# Arduino_Shield.net
KiCad netlist of a schematic drawn in Altium Designer
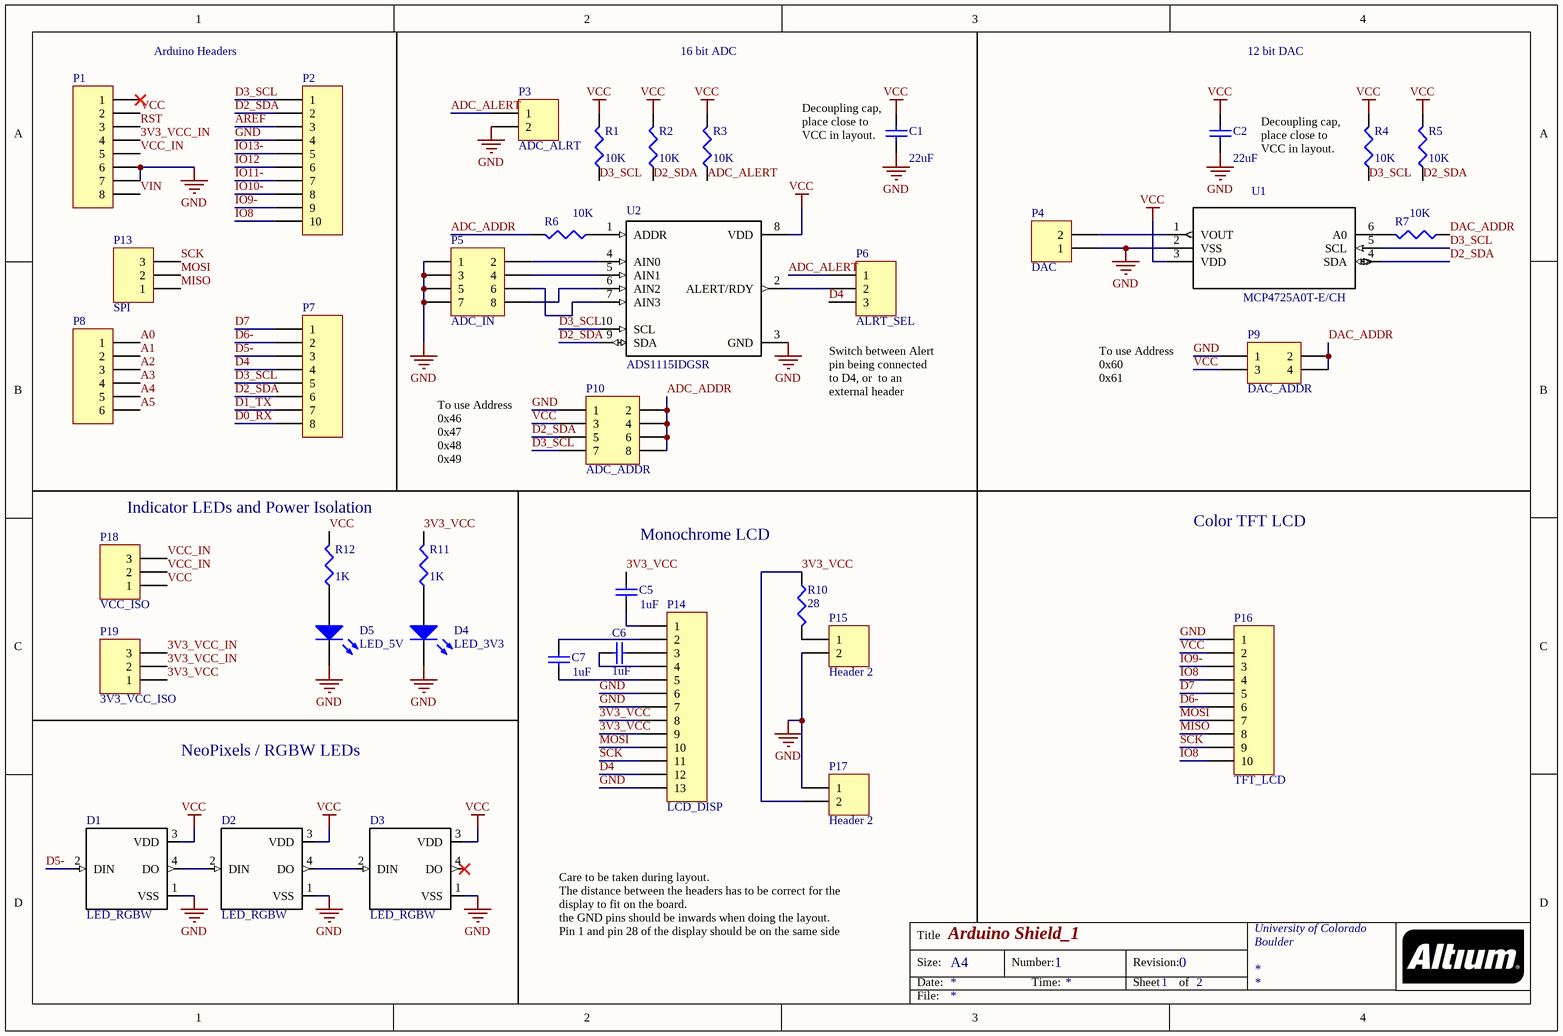
[diagram p0: Arduino_Shield.SchDoc]

(export (version "E")
  (design (tool "Eeschema 10.0.6"))
  (components
    (comp (ref "C1")
      (value "22uF")
      (footprint "C1206")
      (description "Capacitor (Semiconductor SIM Model)")
      (fields
        (field (name "DIGIKEYPARTNO") "1276-1079-1-ND")
        (field (name "Comment") "Cap Semi")
        (field (name "PUBLISHER") "Altium Limited")
      )
      (libsource (lib "Miscellaneous Devices") (part "Cap Semi"))
    )
    (comp (ref "C2")
      (value "22uF")
      (footprint "C1206")
      (description "Capacitor (Semiconductor SIM Model)")
      (fields
        (field (name "DIGIKEYPARTNO") "1276-1079-1-ND")
        (field (name "Comment") "Cap Semi")
        (field (name "PUBLISHER") "Altium Limited")
      )
      (libsource (lib "Miscellaneous Devices") (part "Cap Semi"))
    )
    (comp (ref "C5")
      (value "1uF")
      (footprint "C1206")
      (description "Capacitor (Semiconductor SIM Model)")
      (fields
        (field (name "DIGIKEYPARTNO") "732-7692-1-ND")
        (field (name "Comment") "Cap Semi")
        (field (name "PUBLISHER") "Altium Limited")
      )
      (libsource (lib "Miscellaneous Devices") (part "Cap Semi"))
    )
    (comp (ref "C6")
      (value "1uF")
      (footprint "C1206")
      (description "Capacitor (Semiconductor SIM Model)")
      (fields
        (field (name "DIGIKEYPARTNO") "732-7692-1-ND")
        (field (name "Comment") "Cap Semi")
        (field (name "PUBLISHER") "Altium Limited")
      )
      (libsource (lib "Miscellaneous Devices") (part "Cap Semi"))
    )
    (comp (ref "C7")
      (value "1uF")
      (footprint "C1206")
      (description "Capacitor (Semiconductor SIM Model)")
      (fields
        (field (name "DIGIKEYPARTNO") "732-7692-1-ND")
        (field (name "Comment") "Cap Semi")
        (field (name "PUBLISHER") "Altium Limited")
      )
      (libsource (lib "Miscellaneous Devices") (part "Cap Semi"))
    )
    (comp (ref "D1")
      (value "LED_RGBW")
      (footprint "*LED_IN-PI554FCH")
      (description "5050RGB with integrated IC built in 4 PIN Â•Viewing angle: 120 degrees")
      (fields (field (name "MP") "IN-PI554FCH") (field (name "MF") "Inolux"))
      (libsource (lib "IN-PI554FCH") (part "IN-PI554FCH"))
    )
    (comp (ref "D2")
      (value "LED_RGBW")
      (footprint "*LED_IN-PI554FCH")
      (description "5050RGB with integrated IC built in 4 PIN Â•Viewing angle: 120 degrees")
      (fields (field (name "MP") "IN-PI554FCH") (field (name "MF") "Inolux"))
      (libsource (lib "IN-PI554FCH") (part "IN-PI554FCH"))
    )
    (comp (ref "D3")
      (value "LED_RGBW")
      (footprint "*LED_IN-PI554FCH")
      (description "5050RGB with integrated IC built in 4 PIN Â•Viewing angle: 120 degrees")
      (fields (field (name "MP") "IN-PI554FCH") (field (name "MF") "Inolux"))
      (libsource (lib "IN-PI554FCH") (part "IN-PI554FCH"))
    )
    (comp (ref "D4")
      (value "LED_3V3")
      (footprint "3.2X1.6X1.1")
      (description "Typical RED, GREEN, YELLOW, AMBER GaAs LED")
      (fields (field (name "PUBLISHER") "Altium Limited"))
      (libsource (lib "Miscellaneous Devices") (part "LED2"))
    )
    (comp (ref "D5")
      (value "LED_5V")
      (footprint "3.2X1.6X1.1")
      (description "Typical RED, GREEN, YELLOW, AMBER GaAs LED")
      (fields (field (name "PUBLISHER") "Altium Limited"))
      (libsource (lib "Miscellaneous Devices") (part "LED2"))
    )
    (comp (ref "P1")
      (value "P4")
      (footprint "HDR1X8")
      (description "Header, 8-Pin")
      (fields (field (name "DIGIKEYPARTNO") "1568-1413-ND") (field (name "PUBLISHER") "Altium Limited"))
      (libsource (lib "Miscellaneous Connectors") (part "Header 8"))
    )
    (comp (ref "P2")
      (value "P1")
      (footprint "HDR1X10")
      (description "Header, 10-Pin")
      (fields (field (name "DIGIKEYPARTNO") "1568-1413-ND") (field (name "PUBLISHER") "Altium Limited"))
      (libsource (lib "Miscellaneous Connectors") (part "Header 10"))
    )
    (comp (ref "P3")
      (value "ADC_ALRT")
      (footprint "HDR1X2")
      (description "Header, 2-Pin")
      (fields (field (name "DIGIKEYPARTNO") "732-5315-ND") (field (name "PUBLISHER") "Altium Limited"))
      (libsource (lib "") (part "Header 2_1"))
    )
    (comp (ref "P4")
      (value "DAC")
      (footprint "HDR1X2")
      (description "Header, 2-Pin")
      (fields (field (name "DIGIKEYPARTNO") "732-5315-ND") (field (name "PUBLISHER") "Altium Limited"))
      (libsource (lib "Miscellaneous Connectors") (part "Header 2"))
    )
    (comp (ref "P5")
      (value "ADC_IN")
      (footprint "HDR2X4")
      (description "Header, 4-Pin, Dual row")
      (fields (field (name "DIGIKEYPARTNO") "952-2121-ND") (field (name "PUBLISHER") "Altium Limited"))
      (libsource (lib "Miscellaneous Connectors") (part "Header 4X2"))
    )
    (comp (ref "P6")
      (value "ALRT_SEL")
      (footprint "HDR1X3")
      (description "Header, 3-Pin")
      (fields (field (name "DIGIKEYPARTNO") "732-5315-ND") (field (name "PUBLISHER") "Altium Limited"))
      (libsource (lib "Miscellaneous Connectors") (part "Header 3"))
    )
    (comp (ref "P7")
      (value "P2")
      (footprint "HDR1X8")
      (description "Header, 8-Pin")
      (fields (field (name "DIGIKEYPARTNO") "1568-1413-ND") (field (name "PUBLISHER") "Altium Limited"))
      (libsource (lib "") (part "Header 8_1"))
    )
    (comp (ref "P8")
      (value "P3")
      (footprint "HDR1X6")
      (description "Header, 6-Pin")
      (fields (field (name "DIGIKEYPARTNO") "1568-1413-ND") (field (name "PUBLISHER") "Altium Limited"))
      (libsource (lib "Miscellaneous Connectors") (part "Header 6"))
    )
    (comp (ref "P9")
      (value "DAC_ADDR")
      (footprint "HDR2X2")
      (description "Header, 2-Pin, Dual row")
      (fields (field (name "DIGIKEYPARTNO") "952-2121-ND") (field (name "PUBLISHER") "Altium Limited"))
      (libsource (lib "Miscellaneous Connectors") (part "Header 2X2"))
    )
    (comp (ref "P10")
      (value "ADC_ADDR")
      (footprint "HDR2X4")
      (description "Header, 4-Pin, Dual row")
      (fields (field (name "DIGIKEYPARTNO") "952-2121-ND") (field (name "PUBLISHER") "Altium Limited"))
      (libsource (lib "Miscellaneous Connectors") (part "Header 4X2"))
    )
    (comp (ref "P13")
      (value "SPI")
      (footprint "HDR1X3")
      (description "Header, 3-Pin")
      (fields (field (name "DIGIKEYPARTNO") "1568-1413-ND") (field (name "PUBLISHER") "Altium Limited"))
      (libsource (lib "") (part "Header 3_1"))
    )
    (comp (ref "P14")
      (value "LCD_DISP")
      (footprint "HDR1X13")
      (description "Header, 13-Pin")
      (fields (field (name "DIGIKEYPARTNO") "1212-1179-ND") (field (name "PUBLISHER") "Altium Limited"))
      (libsource (lib "Miscellaneous Connectors") (part "Header 13"))
    )
    (comp (ref "P15")
      (value "Header 2")
      (footprint "HDR1X2")
      (description "Header, 2-Pin")
      (fields (field (name "DIGIKEYPARTNO") "1212-1179-ND") (field (name "PUBLISHER") "Altium Limited"))
      (libsource (lib "") (part "Header 2_1"))
    )
    (comp (ref "P16")
      (value "TFT_LCD")
      (footprint "HDR1X10")
      (description "Header, 10-Pin")
      (fields (field (name "DIGIKEYPARTNO") "1212-1179-ND") (field (name "PUBLISHER") "Altium Limited"))
      (libsource (lib "Miscellaneous Connectors") (part "Header 10"))
    )
    (comp (ref "P17")
      (value "Header 2")
      (footprint "HDR1X2")
      (description "Header, 2-Pin")
      (fields (field (name "DIGIKEYPARTNO") "1212-1179-ND") (field (name "PUBLISHER") "Altium Limited"))
      (libsource (lib "") (part "Header 2_1"))
    )
    (comp (ref "P18")
      (value "VCC_ISO")
      (footprint "HDR1X3")
      (description "Header, 3-Pin")
      (fields (field (name "DIGIKEYPARTNO") "1568-1413-ND") (field (name "PUBLISHER") "Altium Limited"))
      (libsource (lib "") (part "Header 3_1"))
    )
    (comp (ref "P19")
      (value "3V3_VCC_ISO")
      (footprint "HDR1X3")
      (description "Header, 3-Pin")
      (fields (field (name "DIGIKEYPARTNO") "1568-1413-ND") (field (name "PUBLISHER") "Altium Limited"))
      (libsource (lib "") (part "Header 3_1"))
    )
    (comp (ref "R1")
      (value "10K")
      (footprint "C1206")
      (description "Resistor")
      (fields
        (field (name "DIGIKEYPARTNO") "RMCF1206JT10K0CT-ND")
        (field (name "Comment") "Res3")
        (field (name "PUBLISHER") "Altium Limited")
      )
      (libsource (lib "Miscellaneous Devices") (part "Res3"))
    )
    (comp (ref "R2")
      (value "10K")
      (footprint "C1206")
      (description "Resistor")
      (fields
        (field (name "DIGIKEYPARTNO") "RMCF1206JT10K0CT-ND")
        (field (name "Comment") "Res3")
        (field (name "PUBLISHER") "Altium Limited")
      )
      (libsource (lib "Miscellaneous Devices") (part "Res3"))
    )
    (comp (ref "R3")
      (value "10K")
      (footprint "C1206")
      (description "Resistor")
      (fields
        (field (name "DIGIKEYPARTNO") "RMCF1206JT10K0CT-ND")
        (field (name "Comment") "Res3")
        (field (name "PUBLISHER") "Altium Limited")
      )
      (libsource (lib "Miscellaneous Devices") (part "Res3"))
    )
    (comp (ref "R4")
      (value "10K")
      (footprint "C1206")
      (description "Resistor")
      (fields
        (field (name "DIGIKEYPARTNO") "RMCF1206JT10K0CT-ND")
        (field (name "Comment") "Res3")
        (field (name "PUBLISHER") "Altium Limited")
      )
      (libsource (lib "Miscellaneous Devices") (part "Res3"))
    )
    (comp (ref "R5")
      (value "10K")
      (footprint "C1206")
      (description "Resistor")
      (fields
        (field (name "DIGIKEYPARTNO") "RMCF1206JT10K0CT-ND")
        (field (name "Comment") "Res3")
        (field (name "PUBLISHER") "Altium Limited")
      )
      (libsource (lib "Miscellaneous Devices") (part "Res3"))
    )
    (comp (ref "R6")
      (value "10K")
      (footprint "C1206")
      (description "Resistor")
      (fields
        (field (name "DIGIKEYPARTNO") "RMCF1206JT10K0CT-ND")
        (field (name "Comment") "Res3")
        (field (name "PUBLISHER") "Altium Limited")
      )
      (libsource (lib "Miscellaneous Devices") (part "Res3"))
    )
    (comp (ref "R7")
      (value "10K")
      (footprint "C1206")
      (description "Resistor")
      (fields
        (field (name "DIGIKEYPARTNO") "RMCF1206JT10K0CT-ND")
        (field (name "Comment") "Res3")
        (field (name "PUBLISHER") "Altium Limited")
      )
      (libsource (lib "Miscellaneous Devices") (part "Res3"))
    )
    (comp (ref "R10")
      (value "28")
      (footprint "C1206")
      (description "Resistor")
      (fields
        (field (name "DIGIKEYPARTNO") "RMCF1206FT28R0")
        (field (name "Comment") "Res3")
        (field (name "PUBLISHER") "Altium Limited")
      )
      (libsource (lib "Miscellaneous Devices") (part "Res3"))
    )
    (comp (ref "R11")
      (value "1K")
      (footprint "C1206")
      (description "Resistor")
      (fields (field (name "Comment") "Res3") (field (name "PUBLISHER") "Altium Limited"))
      (libsource (lib "Miscellaneous Devices") (part "Res3"))
    )
    (comp (ref "R12")
      (value "1K")
      (footprint "C1206")
      (description "Resistor")
      (fields (field (name "Comment") "Res3") (field (name "PUBLISHER") "Altium Limited"))
      (libsource (lib "Miscellaneous Devices") (part "Res3"))
    )
    (comp (ref "U1")
      (value "MCP4725A0T-E/CH")
      (footprint "*SOT95P270X145-6N")
      (description "MCP4725 Series 1 Ch I2C EEPROM Memory 5.5 V 12-Bit D/A Converter SMT - SOT-23-6")
      (fields (field (name "MF") "Microchip") (field (name "DIGIKEYPARTNO") "MCP4725A0T-E/CHCT-ND"))
      (libsource (lib "MCP4725A0T-E_CH") (part "MCP4725A0T-E/CH"))
    )
    (comp (ref "U2")
      (value "ADS1115IDGSR")
      (footprint "*SOP50P490X110-10N")
      (description "16-Bit ADC with Integrated MUX, PGA, Comparator, Oscillator, and Reference 10-VSSOP -40 to 125")
      (fields (field (name "MF") "Texas Instruments") (field (name "DIGIKEYPARTNO") "296-38849-1-ND"))
      (libsource (lib "ADS1115IDGSR") (part "ADS1115IDGSR"))
    )
  )
  (nets
    (net (code "1") (name "/3V3_VCC") (class "Default")
      (node (ref "C5") (pin "2") (pinfunction "2_2") (pintype "passive"))
      (node (ref "P14") (pin "8") (pinfunction "8_8") (pintype "passive"))
      (node (ref "P14") (pin "9") (pinfunction "9_9") (pintype "passive"))
      (node (ref "P17") (pin "2") (pinfunction "2_2") (pintype "passive"))
      (node (ref "P19") (pin "1") (pinfunction "1_1") (pintype "passive"))
      (node (ref "R10") (pin "1") (pinfunction "1_1") (pintype "passive"))
      (node (ref "R11") (pin "2") (pinfunction "2_2") (pintype "passive"))
    )
    (net (code "2") (name "/3V3_VCC_IN") (class "Default")
      (node (ref "P1") (pin "4") (pinfunction "4_4") (pintype "passive"))
      (node (ref "P19") (pin "2") (pinfunction "2_2") (pintype "passive"))
      (node (ref "P19") (pin "3") (pinfunction "3_3") (pintype "passive"))
    )
    (net (code "3") (name "/A0") (class "Default")
      (node (ref "P8") (pin "1") (pinfunction "1_1") (pintype "passive"))
    )
    (net (code "4") (name "/A1") (class "Default")
      (node (ref "P8") (pin "2") (pinfunction "2_2") (pintype "passive"))
    )
    (net (code "5") (name "/A2") (class "Default")
      (node (ref "P8") (pin "3") (pinfunction "3_3") (pintype "passive"))
    )
    (net (code "6") (name "/A3") (class "Default")
      (node (ref "P8") (pin "4") (pinfunction "4_4") (pintype "passive"))
    )
    (net (code "7") (name "/A4") (class "Default")
      (node (ref "P8") (pin "5") (pinfunction "5_5") (pintype "passive"))
    )
    (net (code "8") (name "/A5") (class "Default")
      (node (ref "P8") (pin "6") (pinfunction "6_6") (pintype "passive"))
    )
    (net (code "9") (name "/ADC_ADDR") (class "Default")
      (node (ref "P10") (pin "2") (pinfunction "2_2") (pintype "passive"))
      (node (ref "P10") (pin "4") (pinfunction "4_4") (pintype "passive"))
      (node (ref "P10") (pin "6") (pinfunction "6_6") (pintype "passive"))
      (node (ref "P10") (pin "8") (pinfunction "8_8") (pintype "passive"))
      (node (ref "R6") (pin "2") (pinfunction "2_2") (pintype "passive"))
    )
    (net (code "10") (name "/ADC_ALERT") (class "Default")
      (node (ref "P3") (pin "1") (pinfunction "1_1") (pintype "passive"))
      (node (ref "P6") (pin "1") (pinfunction "1_1") (pintype "passive"))
      (node (ref "R3") (pin "1") (pinfunction "1_1") (pintype "passive"))
    )
    (net (code "11") (name "/AREF") (class "Default")
      (node (ref "P2") (pin "3") (pinfunction "3_3") (pintype "passive"))
    )
    (net (code "12") (name "/D0_RX") (class "Default")
      (node (ref "P7") (pin "8") (pinfunction "8_8") (pintype "passive"))
    )
    (net (code "13") (name "/D1_TX") (class "Default")
      (node (ref "P7") (pin "7") (pinfunction "7_7") (pintype "passive"))
    )
    (net (code "14") (name "/D2_SDA") (class "Default")
      (node (ref "P10") (pin "5") (pinfunction "5_5") (pintype "passive"))
      (node (ref "P2") (pin "2") (pinfunction "2_2") (pintype "passive"))
      (node (ref "P7") (pin "6") (pinfunction "6_6") (pintype "passive"))
      (node (ref "R2") (pin "1") (pinfunction "1_1") (pintype "passive"))
      (node (ref "R5") (pin "1") (pinfunction "1_1") (pintype "passive"))
      (node (ref "U1") (pin "4") (pinfunction "SDA_4") (pintype "bidirectional"))
      (node (ref "U2") (pin "9") (pinfunction "SDA_9") (pintype "bidirectional"))
    )
    (net (code "15") (name "/D3_SCL") (class "Default")
      (node (ref "P10") (pin "7") (pinfunction "7_7") (pintype "passive"))
      (node (ref "P2") (pin "1") (pinfunction "1_1") (pintype "passive"))
      (node (ref "P7") (pin "5") (pinfunction "5_5") (pintype "passive"))
      (node (ref "R1") (pin "1") (pinfunction "1_1") (pintype "passive"))
      (node (ref "R4") (pin "1") (pinfunction "1_1") (pintype "passive"))
      (node (ref "U1") (pin "5") (pinfunction "SCL_5") (pintype "input"))
      (node (ref "U2") (pin "10") (pinfunction "SCL_10") (pintype "input"))
    )
    (net (code "16") (name "/D4") (class "Default")
      (node (ref "P14") (pin "12") (pinfunction "12_12") (pintype "passive"))
      (node (ref "P6") (pin "3") (pinfunction "3_3") (pintype "passive"))
      (node (ref "P7") (pin "4") (pinfunction "4_4") (pintype "passive"))
    )
    (net (code "17") (name "/D5-") (class "Default")
      (node (ref "D1") (pin "2") (pinfunction "DIN_2") (pintype "input"))
      (node (ref "P7") (pin "3") (pinfunction "3_3") (pintype "passive"))
    )
    (net (code "18") (name "/D6-") (class "Default")
      (node (ref "P16") (pin "6") (pinfunction "6_6") (pintype "passive"))
      (node (ref "P7") (pin "2") (pinfunction "2_2") (pintype "passive"))
    )
    (net (code "19") (name "/D7") (class "Default")
      (node (ref "P16") (pin "5") (pinfunction "5_5") (pintype "passive"))
      (node (ref "P7") (pin "1") (pinfunction "1_1") (pintype "passive"))
    )
    (net (code "20") (name "/DAC_ADDR") (class "Default")
      (node (ref "P9") (pin "2") (pinfunction "2_2") (pintype "passive"))
      (node (ref "P9") (pin "4") (pinfunction "4_4") (pintype "passive"))
      (node (ref "R7") (pin "1") (pinfunction "1_1") (pintype "passive"))
    )
    (net (code "21") (name "/IO8") (class "Default")
      (node (ref "P16") (pin "10") (pinfunction "10_10") (pintype "passive"))
      (node (ref "P16") (pin "4") (pinfunction "4_4") (pintype "passive"))
      (node (ref "P2") (pin "10") (pinfunction "10_10") (pintype "passive"))
    )
    (net (code "22") (name "/IO9-") (class "Default")
      (node (ref "P16") (pin "3") (pinfunction "3_3") (pintype "passive"))
      (node (ref "P2") (pin "9") (pinfunction "9_9") (pintype "passive"))
    )
    (net (code "23") (name "/IO10-") (class "Default")
      (node (ref "P2") (pin "8") (pinfunction "8_8") (pintype "passive"))
    )
    (net (code "24") (name "/IO11-") (class "Default")
      (node (ref "P2") (pin "7") (pinfunction "7_7") (pintype "passive"))
    )
    (net (code "25") (name "/IO12") (class "Default")
      (node (ref "P2") (pin "6") (pinfunction "6_6") (pintype "passive"))
    )
    (net (code "26") (name "/IO13-") (class "Default")
      (node (ref "P2") (pin "5") (pinfunction "5_5") (pintype "passive"))
    )
    (net (code "27") (name "/MISO") (class "Default")
      (node (ref "P13") (pin "1") (pinfunction "1_1") (pintype "passive"))
      (node (ref "P16") (pin "8") (pinfunction "8_8") (pintype "passive"))
    )
    (net (code "28") (name "/MOSI") (class "Default")
      (node (ref "P13") (pin "2") (pinfunction "2_2") (pintype "passive"))
      (node (ref "P14") (pin "10") (pinfunction "10_10") (pintype "passive"))
      (node (ref "P16") (pin "7") (pinfunction "7_7") (pintype "passive"))
    )
    (net (code "29") (name "/RST") (class "Default")
      (node (ref "P1") (pin "3") (pinfunction "3_3") (pintype "passive"))
    )
    (net (code "30") (name "/SCK") (class "Default")
      (node (ref "P13") (pin "3") (pinfunction "3_3") (pintype "passive"))
      (node (ref "P14") (pin "11") (pinfunction "11_11") (pintype "passive"))
      (node (ref "P16") (pin "9") (pinfunction "9_9") (pintype "passive"))
    )
    (net (code "31") (name "/VCC_IN") (class "Default")
      (node (ref "P1") (pin "5") (pinfunction "5_5") (pintype "passive"))
      (node (ref "P18") (pin "2") (pinfunction "2_2") (pintype "passive"))
      (node (ref "P18") (pin "3") (pinfunction "3_3") (pintype "passive"))
    )
    (net (code "32") (name "/VIN") (class "Default")
      (node (ref "P1") (pin "8") (pinfunction "8_8") (pintype "passive"))
    )
    (net (code "33") (name "GND") (class "Default")
      (node (ref "C1") (pin "1") (pinfunction "1_1") (pintype "passive"))
      (node (ref "C2") (pin "1") (pinfunction "1_1") (pintype "passive"))
      (node (ref "D1") (pin "1") (pinfunction "VSS_1") (pintype "power_in"))
      (node (ref "D2") (pin "1") (pinfunction "VSS_1") (pintype "power_in"))
      (node (ref "D3") (pin "1") (pinfunction "VSS_1") (pintype "power_in"))
      (node (ref "D4") (pin "2") (pinfunction "K_2") (pintype "passive"))
      (node (ref "D5") (pin "2") (pinfunction "K_2") (pintype "passive"))
      (node (ref "P1") (pin "6") (pinfunction "6_6") (pintype "passive"))
      (node (ref "P1") (pin "7") (pinfunction "7_7") (pintype "passive"))
      (node (ref "P10") (pin "1") (pinfunction "1_1") (pintype "passive"))
      (node (ref "P14") (pin "13") (pinfunction "13_13") (pintype "passive"))
      (node (ref "P14") (pin "6") (pinfunction "6_6") (pintype "passive"))
      (node (ref "P14") (pin "7") (pinfunction "7_7") (pintype "passive"))
      (node (ref "P15") (pin "2") (pinfunction "2_2") (pintype "passive"))
      (node (ref "P16") (pin "1") (pinfunction "1_1") (pintype "passive"))
      (node (ref "P17") (pin "1") (pinfunction "1_1") (pintype "passive"))
      (node (ref "P2") (pin "4") (pinfunction "4_4") (pintype "passive"))
      (node (ref "P3") (pin "2") (pinfunction "2_2") (pintype "passive"))
      (node (ref "P4") (pin "1") (pinfunction "1_1") (pintype "passive"))
      (node (ref "P5") (pin "1") (pinfunction "1_1") (pintype "passive"))
      (node (ref "P5") (pin "3") (pinfunction "3_3") (pintype "passive"))
      (node (ref "P5") (pin "5") (pinfunction "5_5") (pintype "passive"))
      (node (ref "P5") (pin "7") (pinfunction "7_7") (pintype "passive"))
      (node (ref "P9") (pin "1") (pinfunction "1_1") (pintype "passive"))
      (node (ref "U1") (pin "2") (pinfunction "VSS_2") (pintype "power_in"))
      (node (ref "U2") (pin "3") (pinfunction "GND_3") (pintype "power_in"))
    )
    (net (code "34") (name "Net-(C5-Pad1)") (class "Default")
      (node (ref "C5") (pin "1") (pinfunction "1_1") (pintype "passive"))
      (node (ref "P14") (pin "1") (pinfunction "1_1") (pintype "passive"))
    )
    (net (code "35") (name "Net-(C6-Pad1)") (class "Default")
      (node (ref "C6") (pin "1") (pinfunction "1_1") (pintype "passive"))
      (node (ref "P14") (pin "3") (pinfunction "3_3") (pintype "passive"))
    )
    (net (code "36") (name "Net-(C6-Pad2)") (class "Default")
      (node (ref "C6") (pin "2") (pinfunction "2_2") (pintype "passive"))
      (node (ref "P14") (pin "4") (pinfunction "4_4") (pintype "passive"))
    )
    (net (code "37") (name "Net-(C7-Pad1)") (class "Default")
      (node (ref "C7") (pin "1") (pinfunction "1_1") (pintype "passive"))
      (node (ref "P14") (pin "5") (pinfunction "5_5") (pintype "passive"))
    )
    (net (code "38") (name "Net-(C7-Pad2)") (class "Default")
      (node (ref "C7") (pin "2") (pinfunction "2_2") (pintype "passive"))
      (node (ref "P14") (pin "2") (pinfunction "2_2") (pintype "passive"))
    )
    (net (code "39") (name "Net-(D1-DO)") (class "Default")
      (node (ref "D1") (pin "4") (pinfunction "DO_4") (pintype "output"))
      (node (ref "D2") (pin "2") (pinfunction "DIN_2") (pintype "input"))
    )
    (net (code "40") (name "Net-(D2-DO)") (class "Default")
      (node (ref "D2") (pin "4") (pinfunction "DO_4") (pintype "output"))
      (node (ref "D3") (pin "2") (pinfunction "DIN_2") (pintype "input"))
    )
    (net (code "41") (name "Net-(D4-A)") (class "Default")
      (node (ref "D4") (pin "1") (pinfunction "A_1") (pintype "passive"))
      (node (ref "R11") (pin "1") (pinfunction "1_1") (pintype "passive"))
    )
    (net (code "42") (name "Net-(D5-A)") (class "Default")
      (node (ref "D5") (pin "1") (pinfunction "A_1") (pintype "passive"))
      (node (ref "R12") (pin "1") (pinfunction "1_1") (pintype "passive"))
    )
    (net (code "43") (name "Net-(P15-Pad1)") (class "Default")
      (node (ref "P15") (pin "1") (pinfunction "1_1") (pintype "passive"))
      (node (ref "R10") (pin "2") (pinfunction "2_2") (pintype "passive"))
    )
    (net (code "44") (name "Net-(U1-A0)") (class "Default")
      (node (ref "R7") (pin "2") (pinfunction "2_2") (pintype "passive"))
      (node (ref "U1") (pin "6") (pinfunction "A0_6") (pintype "passive"))
    )
    (net (code "45") (name "Net-(U1-VOUT)") (class "Default")
      (node (ref "P4") (pin "2") (pinfunction "2_2") (pintype "passive"))
      (node (ref "U1") (pin "1") (pinfunction "VOUT_1") (pintype "output"))
    )
    (net (code "46") (name "Net-(U2-ADDR)") (class "Default")
      (node (ref "R6") (pin "1") (pinfunction "1_1") (pintype "passive"))
      (node (ref "U2") (pin "1") (pinfunction "ADDR_1") (pintype "input"))
    )
    (net (code "47") (name "Net-(U2-AIN0)") (class "Default")
      (node (ref "P5") (pin "2") (pinfunction "2_2") (pintype "passive"))
      (node (ref "U2") (pin "4") (pinfunction "AIN0_4") (pintype "input"))
    )
    (net (code "48") (name "Net-(U2-AIN1)") (class "Default")
      (node (ref "P5") (pin "4") (pinfunction "4_4") (pintype "passive"))
      (node (ref "U2") (pin "5") (pinfunction "AIN1_5") (pintype "input"))
    )
    (net (code "49") (name "Net-(U2-AIN2)") (class "Default")
      (node (ref "P5") (pin "8") (pinfunction "8_8") (pintype "passive"))
      (node (ref "U2") (pin "6") (pinfunction "AIN2_6") (pintype "input"))
    )
    (net (code "50") (name "Net-(U2-AIN3)") (class "Default")
      (node (ref "P5") (pin "6") (pinfunction "6_6") (pintype "passive"))
      (node (ref "U2") (pin "7") (pinfunction "AIN3_7") (pintype "input"))
    )
    (net (code "51") (name "Net-(U2-ALERT{slash}RDY)") (class "Default")
      (node (ref "P6") (pin "2") (pinfunction "2_2") (pintype "passive"))
      (node (ref "U2") (pin "2") (pinfunction "ALERT/RDY_2") (pintype "output"))
    )
    (net (code "52") (name "VCC") (class "Default")
      (node (ref "C1") (pin "2") (pinfunction "2_2") (pintype "passive"))
      (node (ref "C2") (pin "2") (pinfunction "2_2") (pintype "passive"))
      (node (ref "D1") (pin "3") (pinfunction "VDD_3") (pintype "power_in"))
      (node (ref "D2") (pin "3") (pinfunction "VDD_3") (pintype "power_in"))
      (node (ref "D3") (pin "3") (pinfunction "VDD_3") (pintype "power_in"))
      (node (ref "P1") (pin "2") (pinfunction "2_2") (pintype "passive"))
      (node (ref "P10") (pin "3") (pinfunction "3_3") (pintype "passive"))
      (node (ref "P16") (pin "2") (pinfunction "2_2") (pintype "passive"))
      (node (ref "P18") (pin "1") (pinfunction "1_1") (pintype "passive"))
      (node (ref "P9") (pin "3") (pinfunction "3_3") (pintype "passive"))
      (node (ref "R1") (pin "2") (pinfunction "2_2") (pintype "passive"))
      (node (ref "R12") (pin "2") (pinfunction "2_2") (pintype "passive"))
      (node (ref "R2") (pin "2") (pinfunction "2_2") (pintype "passive"))
      (node (ref "R3") (pin "2") (pinfunction "2_2") (pintype "passive"))
      (node (ref "R4") (pin "2") (pinfunction "2_2") (pintype "passive"))
      (node (ref "R5") (pin "2") (pinfunction "2_2") (pintype "passive"))
      (node (ref "U1") (pin "3") (pinfunction "VDD_3") (pintype "power_in"))
      (node (ref "U2") (pin "8") (pinfunction "VDD_8") (pintype "power_in"))
    )
    (net (code "53") (name "unconnected-(D3-DO-Pad4)") (class "Default")
      (node (ref "D3") (pin "4") (pinfunction "DO_4") (pintype "output+no_connect"))
    )
    (net (code "54") (name "unconnected-(P1-Pad1)") (class "Default")
      (node (ref "P1") (pin "1") (pinfunction "1_1") (pintype "passive+no_connect"))
    )
  )
)
